# power_electronicsV4_4.net
KiCad netlist of a schematic drawn in EAGLE
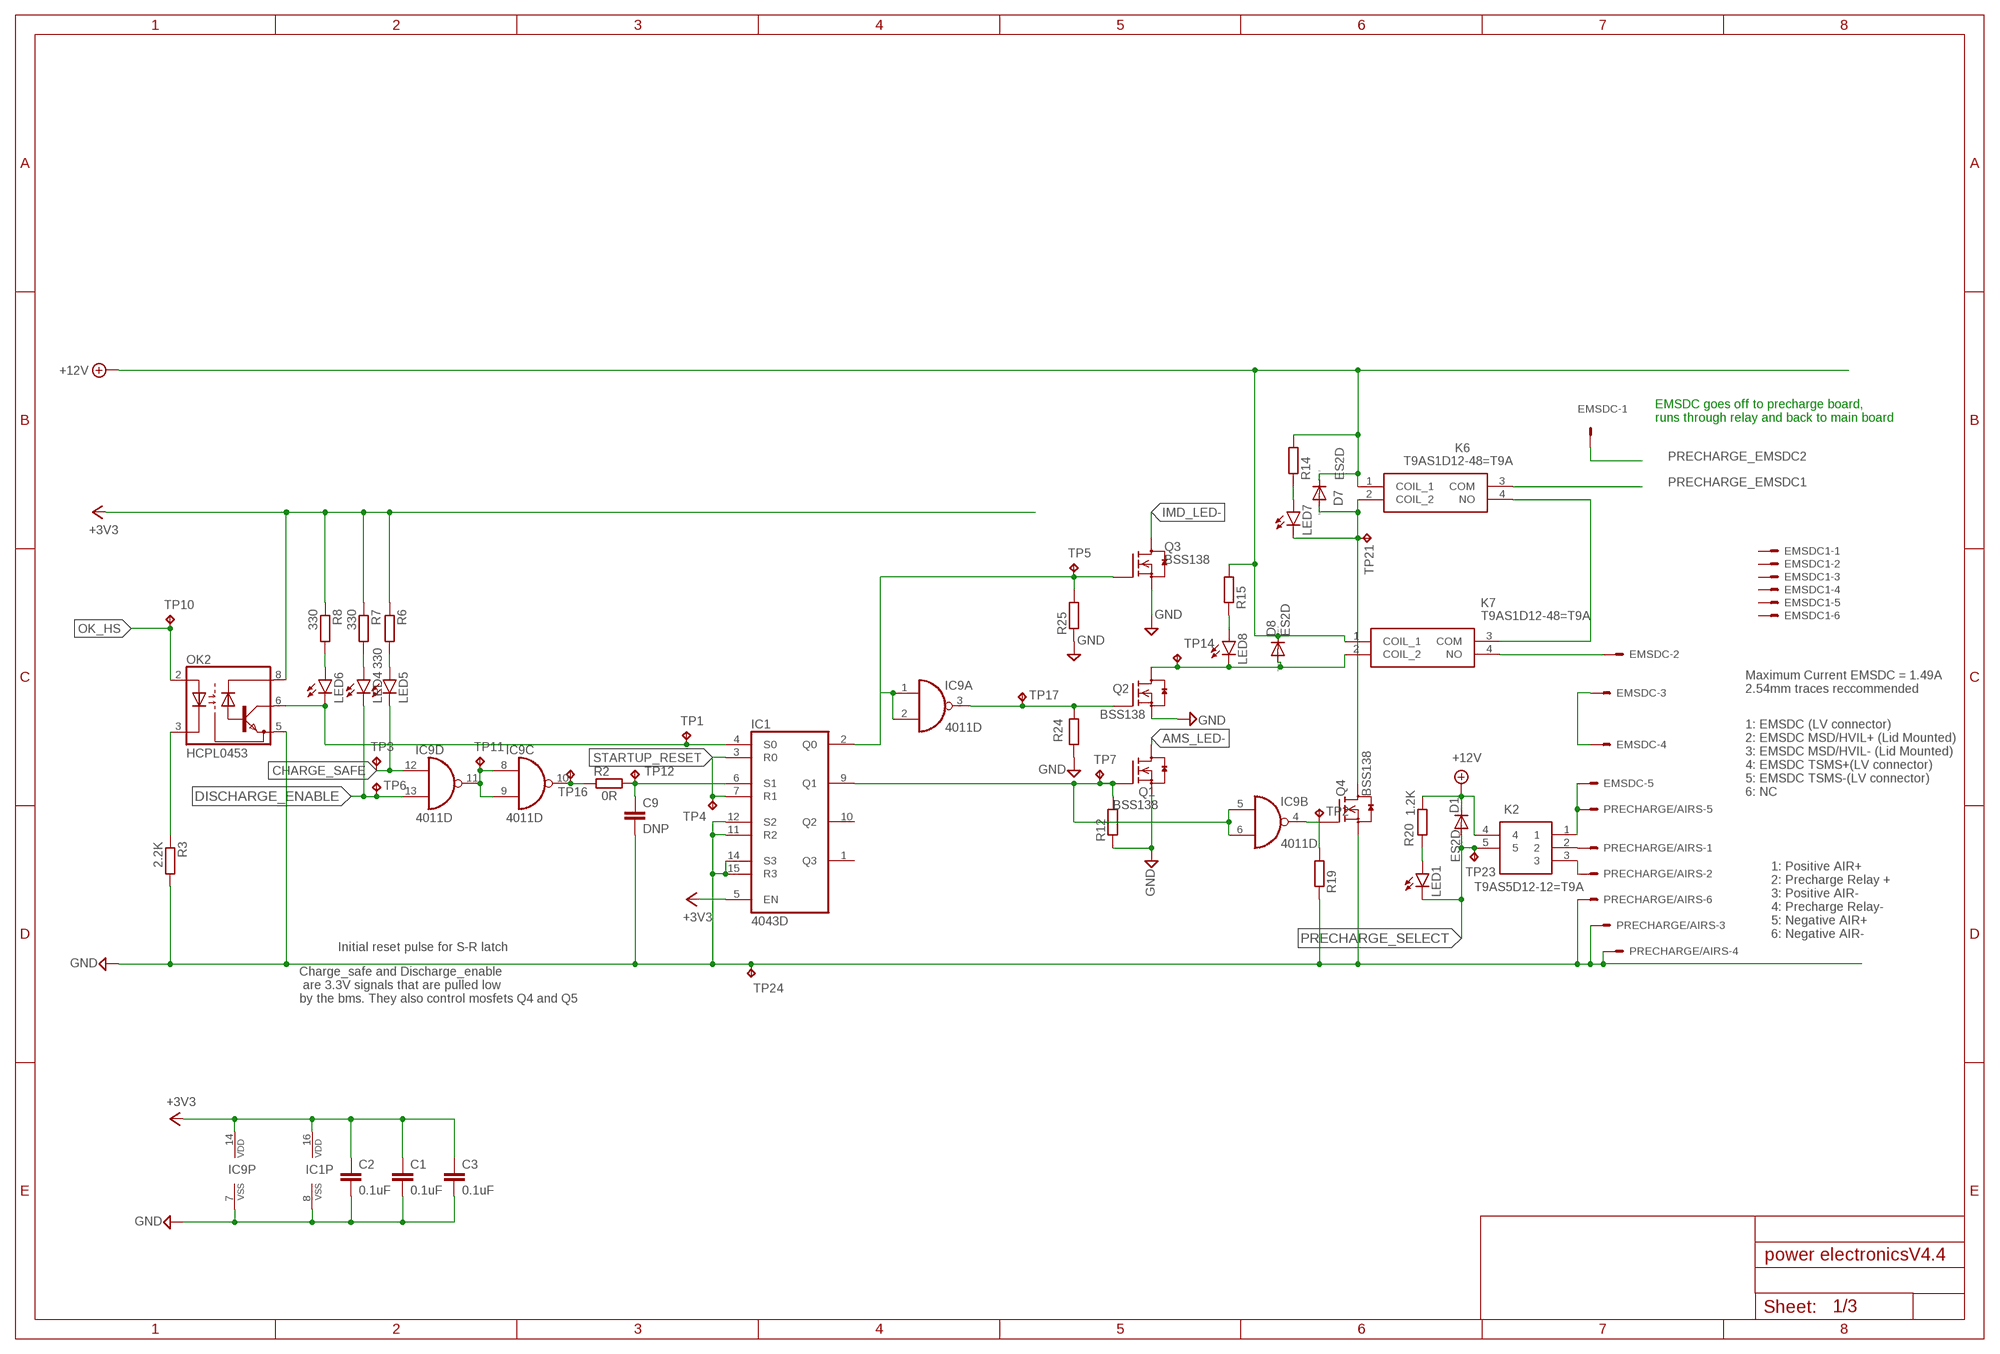
[diagram p0: schematic, sheet 1]
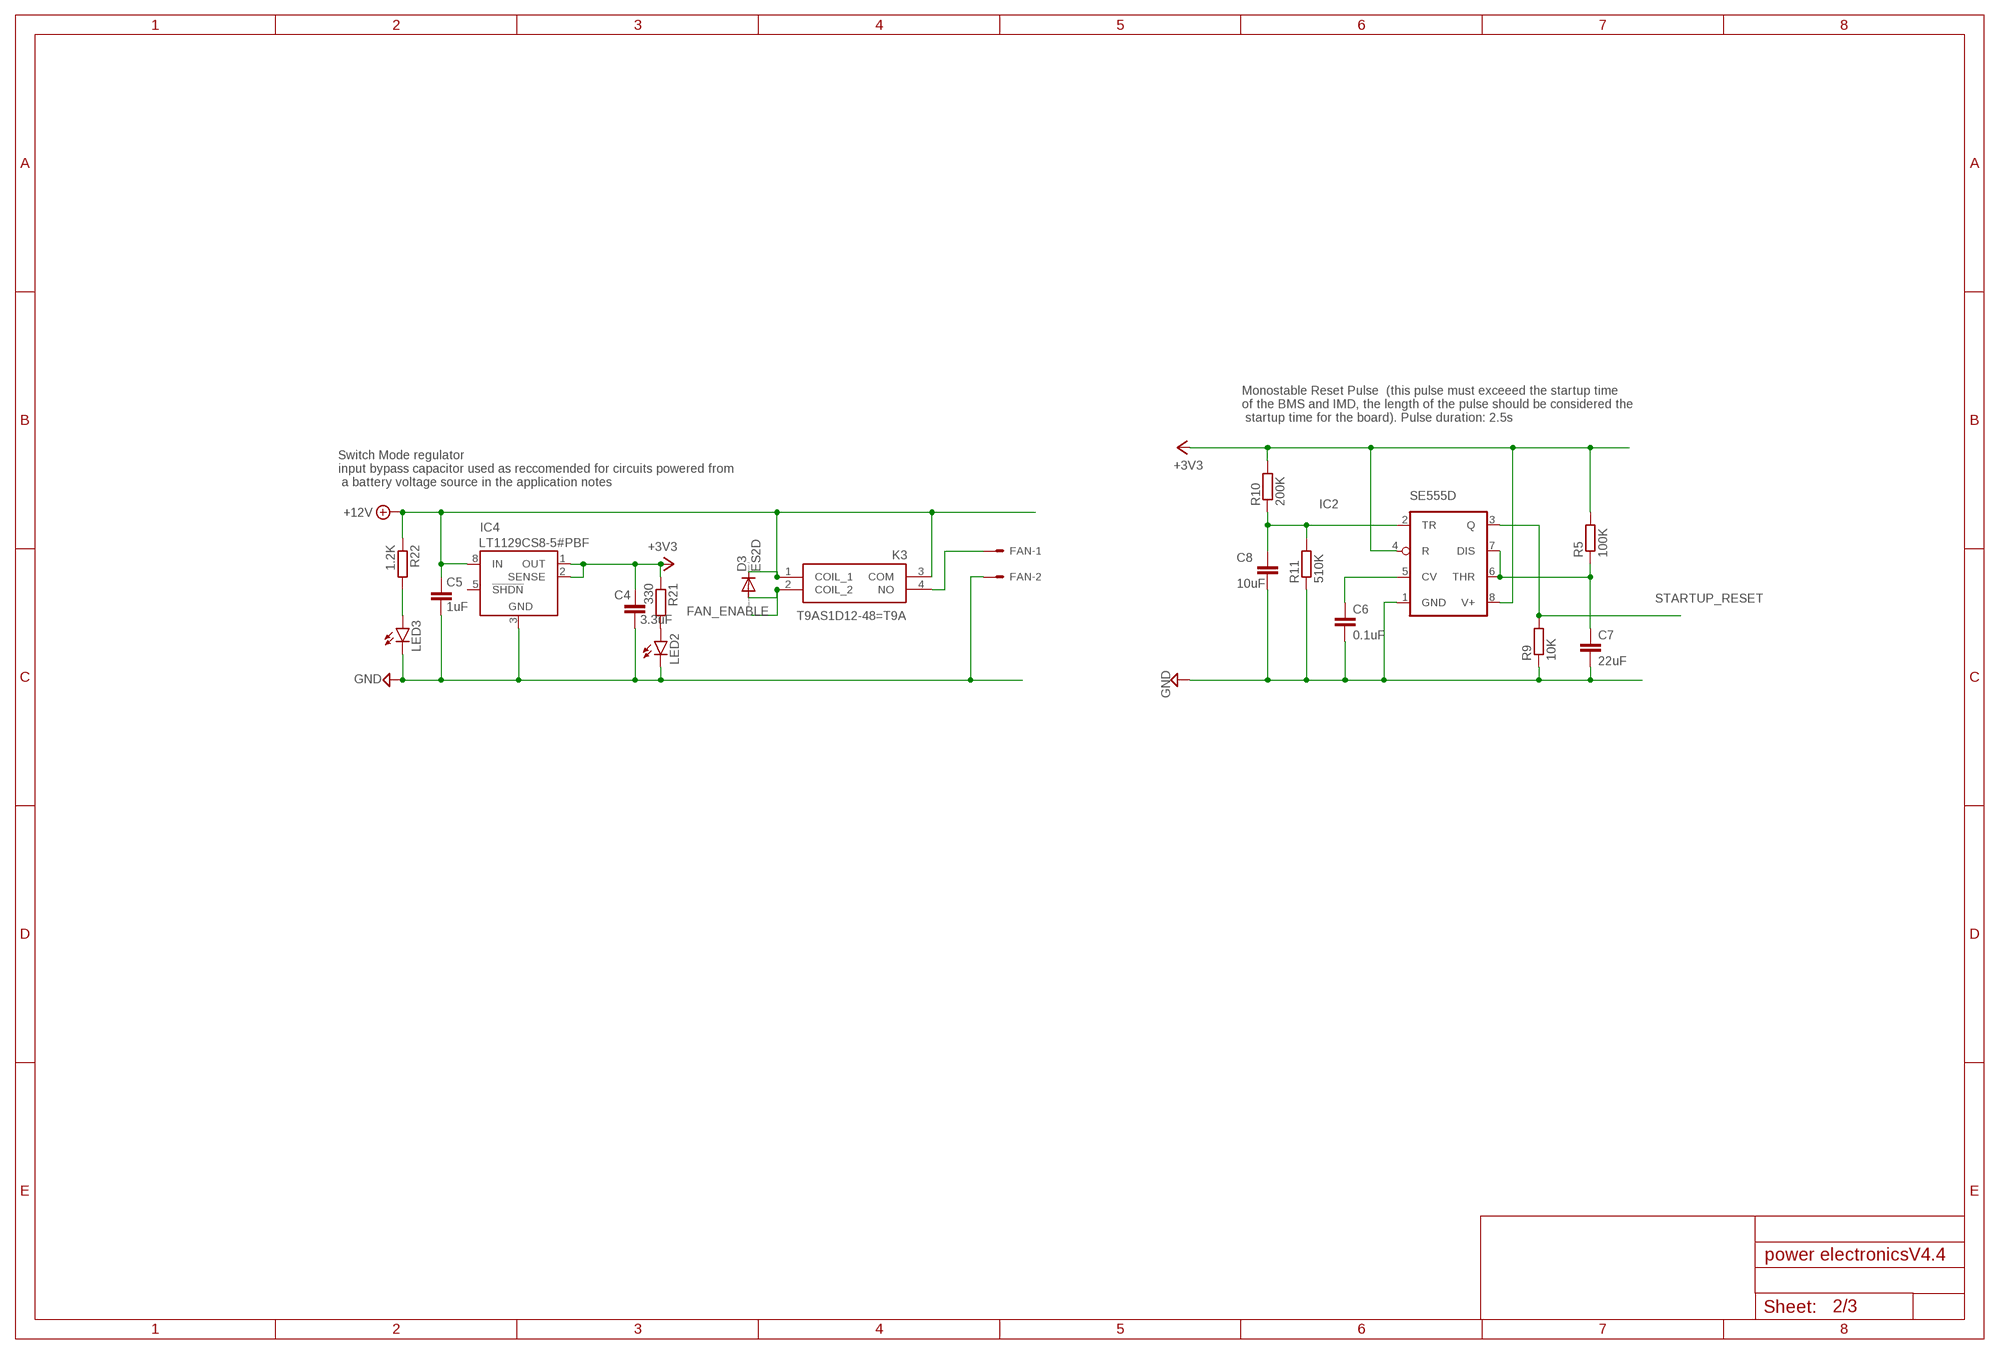
[diagram p1: schematic, sheet 2]
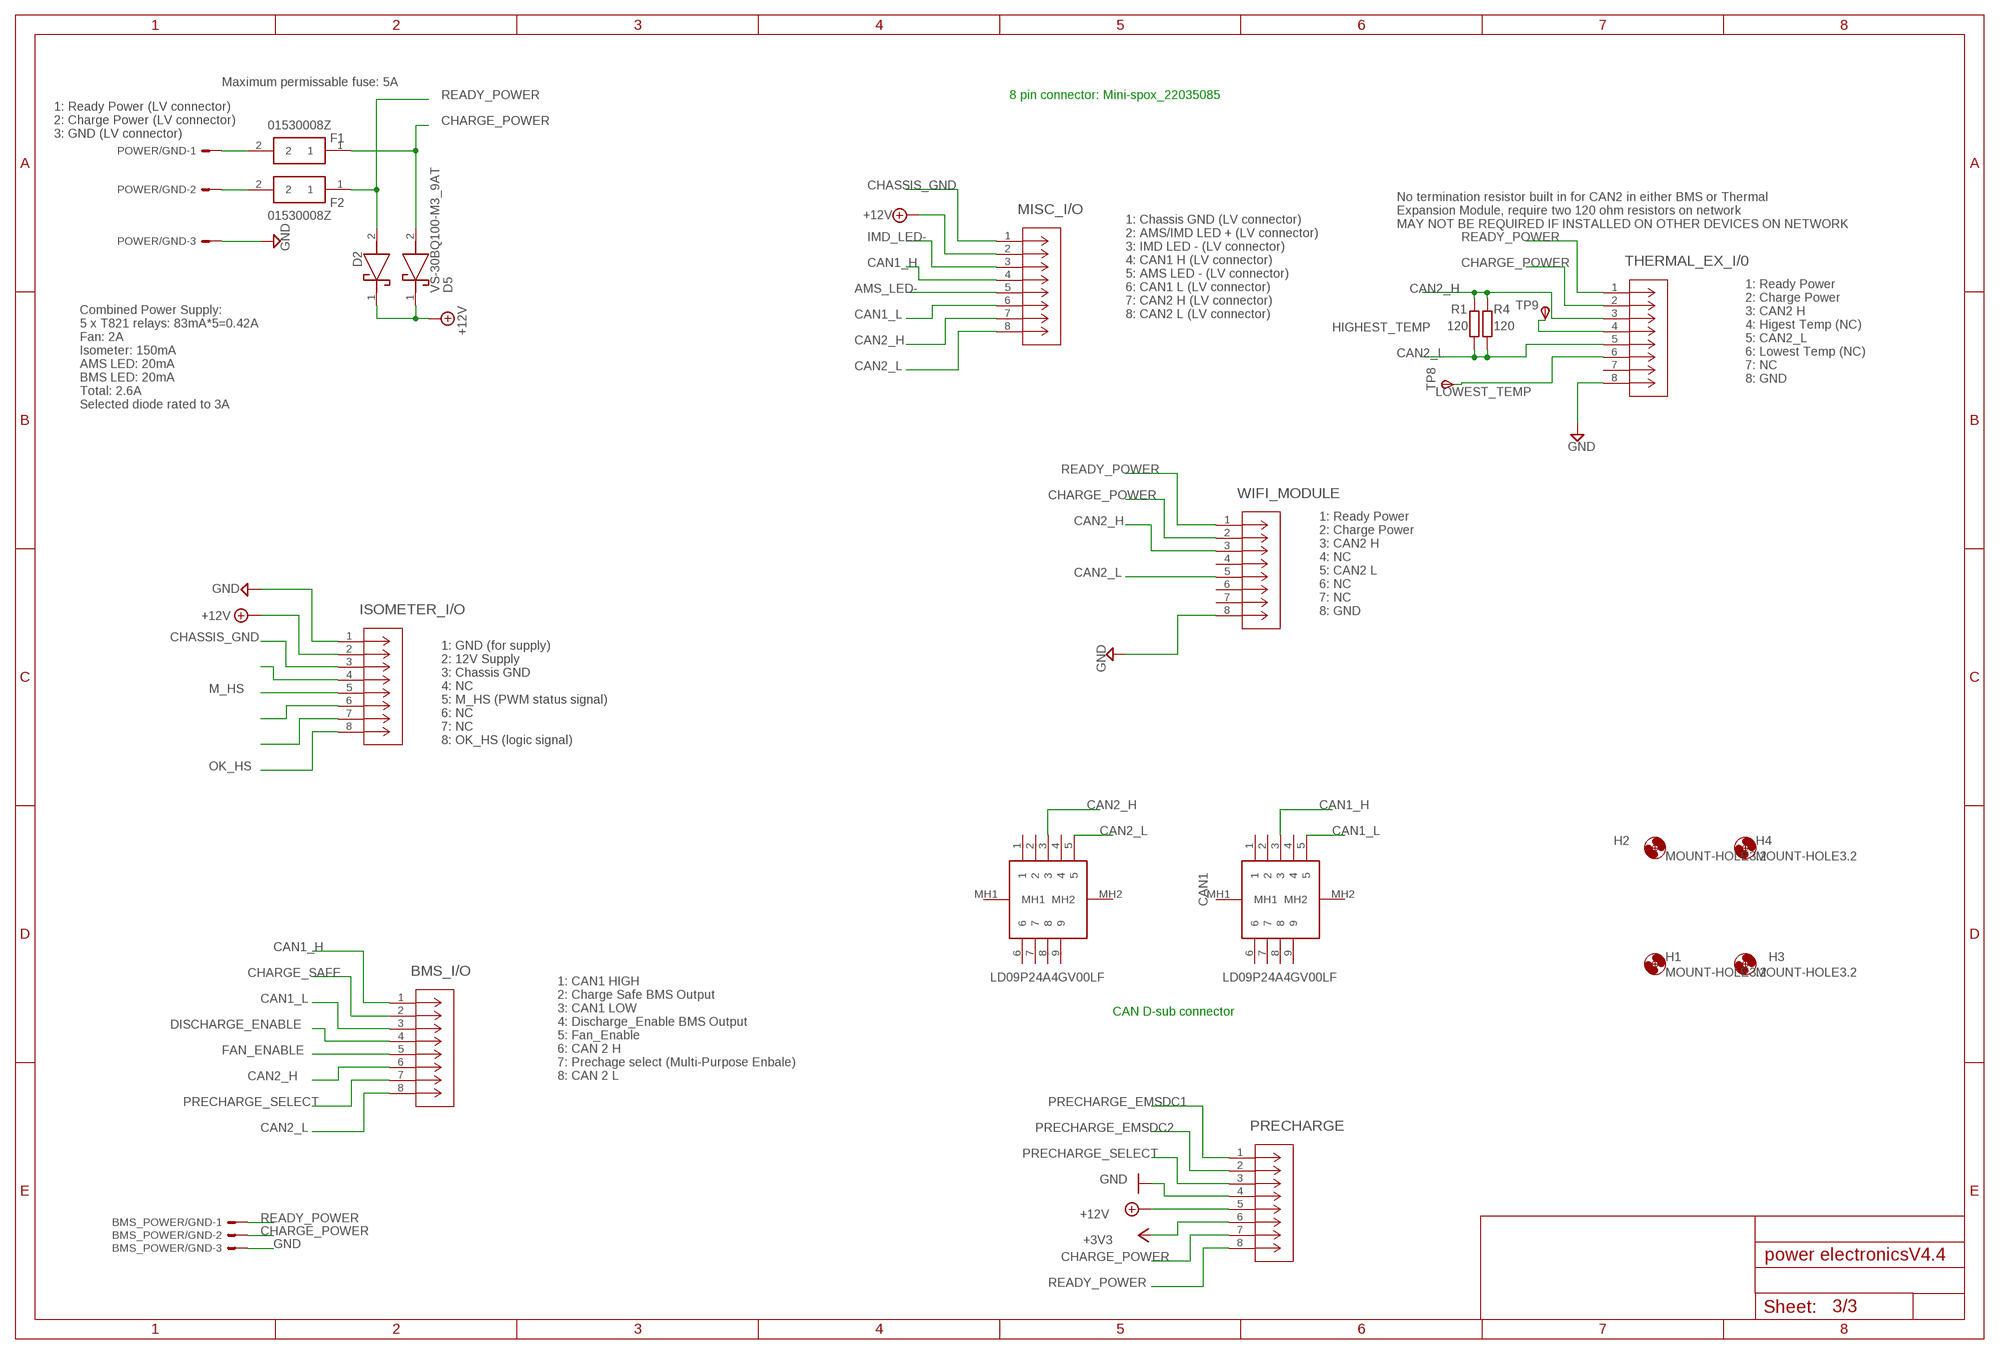
[diagram p2: schematic, sheet 3]

(export (version "E")
  (design (tool "Eeschema 10.0.6"))
  (components
    (comp (ref "BMS_I/O")
      (value "MINI-SPOX_22035085")
      (footprint "eagle-import:CON_22035085_MOL")
      (fields
        (field (name "MANUFACTURER_PART_NUMBER") "22035085")
        (field (name "COPYRIGHT") "Copyright (C) 2023 Ultra Librarian. All rights reserved.")
      )
      (libsource (lib "eagle-import") (part "MINI-SPOX_22035085"))
    )
    (comp (ref "BMS_POWER/GND")
      (value "KK-156-3")
      (footprint "eagle-import:KK-156-3")
      (fields (field (name "MF") "MOLEX"))
      (libsource (lib "eagle-import") (part "KK-156-3"))
    )
    (comp (ref "CAN1")
      (value "LD09P24A4GV00LF")
      (footprint "eagle-import:LD09P24A4GV00LF")
      (fields (field (name "MOUSER_PART_NUMBER") "649-LD09P24A4GV00LF"))
      (libsource (lib "eagle-import") (part "LD09P24A4GV00LF"))
    )
    (comp (ref "CAN2")
      (value "LD09P24A4GV00LF")
      (footprint "eagle-import:LD09P24A4GV00LF")
      (fields (field (name "MOUSER_PART_NUMBER") "649-LD09P24A4GV00LF"))
      (libsource (lib "eagle-import") (part "LD09P24A4GV00LF"))
    )
    (comp (ref "D2")
      (value "VS-30BQ100-M3_9AT")
      (footprint "eagle-import:DIOM7959X262N")
      (fields
        (field (name "MANUFACTURER_PART_NUMBER") "VS-30BQ100-M3/9AT")
        (field (name "MOUSER_PART_NUMBER") "78-VS-30BQ100-M39AT")
      )
      (libsource (lib "eagle-import") (part "VS-30BQ100-M3_9AT"))
    )
    (comp (ref "D5")
      (value "VS-30BQ100-M3_9AT")
      (footprint "eagle-import:DIOM7959X262N")
      (fields
        (field (name "MANUFACTURER_PART_NUMBER") "VS-30BQ100-M3/9AT")
        (field (name "MOUSER_PART_NUMBER") "78-VS-30BQ100-M39AT")
      )
      (libsource (lib "eagle-import") (part "VS-30BQ100-M3_9AT"))
    )
    (comp (ref "F1")
      (value "01530008Z")
      (footprint "eagle-import:01530008")
      (fields (field (name "RS_PART_NUMBER") "3607317"))
      (libsource (lib "eagle-import") (part "01530008Z"))
    )
    (comp (ref "F2")
      (value "01530008Z")
      (footprint "eagle-import:01530008")
      (fields (field (name "RS_PART_NUMBER") "3607317"))
      (libsource (lib "eagle-import") (part "01530008Z"))
    )
    (comp (ref "H1")
      (value "MOUNT-HOLE3.2")
      (footprint "eagle-import:3,2")
      (libsource (lib "eagle-import") (part "MOUNT-HOLE3.2"))
    )
    (comp (ref "H2")
      (value "MOUNT-HOLE3.2")
      (footprint "eagle-import:3,2")
      (libsource (lib "eagle-import") (part "MOUNT-HOLE3.2"))
    )
    (comp (ref "H3")
      (value "MOUNT-HOLE3.2")
      (footprint "eagle-import:3,2")
      (libsource (lib "eagle-import") (part "MOUNT-HOLE3.2"))
    )
    (comp (ref "H4")
      (value "MOUNT-HOLE3.2")
      (footprint "eagle-import:3,2")
      (libsource (lib "eagle-import") (part "MOUNT-HOLE3.2"))
    )
    (comp (ref "ISOMETER_I/O")
      (value "MINI-SPOX_22035085")
      (footprint "eagle-import:CON_22035085_MOL")
      (fields
        (field (name "MANUFACTURER_PART_NUMBER") "22035085")
        (field (name "COPYRIGHT") "Copyright (C) 2023 Ultra Librarian. All rights reserved.")
      )
      (libsource (lib "eagle-import") (part "MINI-SPOX_22035085"))
    )
    (comp (ref "MISC_I/O")
      (value "MINI-SPOX_22035085")
      (footprint "eagle-import:CON_22035085_MOL")
      (fields
        (field (name "MANUFACTURER_PART_NUMBER") "22035085")
        (field (name "COPYRIGHT") "Copyright (C) 2023 Ultra Librarian. All rights reserved.")
      )
      (libsource (lib "eagle-import") (part "MINI-SPOX_22035085"))
    )
    (comp (ref "POWER/GND")
      (value "KK-156-3")
      (footprint "eagle-import:KK-156-3")
      (fields (field (name "MF") "MOLEX"))
      (libsource (lib "eagle-import") (part "KK-156-3"))
    )
    (comp (ref "PRECHARGE")
      (value "MINI-SPOX_22035085")
      (footprint "eagle-import:CON_22035085_MOL")
      (fields
        (field (name "MANUFACTURER_PART_NUMBER") "22035085")
        (field (name "COPYRIGHT") "Copyright (C) 2023 Ultra Librarian. All rights reserved.")
      )
      (libsource (lib "eagle-import") (part "MINI-SPOX_22035085"))
    )
    (comp (ref "R1")
      (value "120")
      (footprint "eagle-import:R1206")
      (libsource (lib "eagle-import") (part "R-EU_R1206"))
    )
    (comp (ref "R4")
      (value "120")
      (footprint "eagle-import:R1206")
      (libsource (lib "eagle-import") (part "R-EU_R1206"))
    )
    (comp (ref "THERMAL_EX_I/0")
      (value "MINI-SPOX_22035085")
      (footprint "eagle-import:CON_22035085_MOL")
      (fields
        (field (name "MANUFACTURER_PART_NUMBER") "22035085")
        (field (name "COPYRIGHT") "Copyright (C) 2023 Ultra Librarian. All rights reserved.")
      )
      (libsource (lib "eagle-import") (part "MINI-SPOX_22035085"))
    )
    (comp (ref "TP8")
      (value "TPSTP11R")
      (footprint "eagle-import:TP11R")
      (libsource (lib "eagle-import") (part "TPSTP11R"))
    )
    (comp (ref "TP9")
      (value "TPSTP11R")
      (footprint "eagle-import:TP11R")
      (libsource (lib "eagle-import") (part "TPSTP11R"))
    )
    (comp (ref "WIFI_MODULE")
      (value "MINI-SPOX_22035085")
      (footprint "eagle-import:CON_22035085_MOL")
      (fields
        (field (name "MANUFACTURER_PART_NUMBER") "22035085")
        (field (name "COPYRIGHT") "Copyright (C) 2023 Ultra Librarian. All rights reserved.")
      )
      (libsource (lib "eagle-import") (part "MINI-SPOX_22035085"))
    )
    (comp (ref "C1")
      (value "0.1uF")
      (footprint "eagle-import:C0805")
      (libsource (lib "eagle-import") (part "C-EUC0805"))
    )
    (comp (ref "C2")
      (value "0.1uF")
      (footprint "eagle-import:C0805")
      (libsource (lib "eagle-import") (part "C-EUC0805"))
    )
    (comp (ref "C3")
      (value "0.1uF")
      (footprint "eagle-import:C0805")
      (libsource (lib "eagle-import") (part "C-EUC0805"))
    )
    (comp (ref "C9")
      (value "DNP")
      (footprint "eagle-import:C0805K")
      (libsource (lib "eagle-import") (part "C-EUC0805K"))
    )
    (comp (ref "D1")
      (value "ES2D")
      (footprint "eagle-import:SMB")
      (libsource (lib "eagle-import") (part "ES2D"))
    )
    (comp (ref "D7")
      (value "ES2D")
      (footprint "eagle-import:SMB")
      (libsource (lib "eagle-import") (part "ES2D"))
    )
    (comp (ref "D8")
      (value "ES2D")
      (footprint "eagle-import:SMB")
      (libsource (lib "eagle-import") (part "ES2D"))
    )
    (comp (ref "EMSDC")
      (value "KK-156-6")
      (footprint "eagle-import:KK-156-6")
      (fields (field (name "MF") "MOLEX"))
      (libsource (lib "eagle-import") (part "KK-156-6"))
    )
    (comp (ref "EMSDC1")
      (value "KK-156-6")
      (footprint "eagle-import:KK-156-6")
      (fields (field (name "MF") "MOLEX"))
      (libsource (lib "eagle-import") (part "KK-156-6"))
    )
    (comp (ref "IC1")
      (value "4043D")
      (footprint "eagle-import:SO16")
      (libsource (lib "eagle-import") (part "4043D"))
    )
    (comp (ref "IC9")
      (value "4011D")
      (footprint "eagle-import:SO14")
      (libsource (lib "eagle-import") (part "4011D"))
    )
    (comp (ref "K2")
      (value "T9AS5D12-12=T9A")
      (footprint "eagle-import:T9AS1D12")
      (fields (field (name "RS_PART_NUMBER") "6802528"))
      (libsource (lib "eagle-import") (part "T9AS5D12-12=T9A"))
    )
    (comp (ref "K6")
      (value "T9AS1D12-48=T9A")
      (footprint "eagle-import:T9AS1D1248T9A")
      (libsource (lib "eagle-import") (part "T9AS1D12-12=T9A_T9AS1D12-48=T9A"))
    )
    (comp (ref "K7")
      (value "T9AS1D12-48=T9A")
      (footprint "eagle-import:T9AS1D1248T9A")
      (libsource (lib "eagle-import") (part "T9AS1D12-12=T9A_T9AS1D12-48=T9A"))
    )
    (comp (ref "LED1")
      (value "LEDSML0805")
      (footprint "eagle-import:SML0805")
      (libsource (lib "eagle-import") (part "LEDSML0805"))
    )
    (comp (ref "LED4")
      (value "LEDSML0805")
      (footprint "eagle-import:SML0805")
      (libsource (lib "eagle-import") (part "LEDSML0805"))
    )
    (comp (ref "LED5")
      (value "LEDSML0805")
      (footprint "eagle-import:SML0805")
      (libsource (lib "eagle-import") (part "LEDSML0805"))
    )
    (comp (ref "LED6")
      (value "LEDSML0805")
      (footprint "eagle-import:SML0805")
      (libsource (lib "eagle-import") (part "LEDSML0805"))
    )
    (comp (ref "LED7")
      (value "LEDSML0805")
      (footprint "eagle-import:SML0805")
      (libsource (lib "eagle-import") (part "LEDSML0805"))
    )
    (comp (ref "LED8")
      (value "LEDSML0805")
      (footprint "eagle-import:SML0805")
      (libsource (lib "eagle-import") (part "LEDSML0805"))
    )
    (comp (ref "OK2")
      (value "HCPL0453")
      (footprint "eagle-import:SOIC08")
      (fields (field (name "MF") "AGILENT TECHNOLOGIES") (field (name "MPN") "HCPL-0453-000E"))
      (libsource (lib "eagle-import") (part "HCPL0453"))
    )
    (comp (ref "PRECHARGE/AIRS")
      (value "KK-156-6")
      (footprint "eagle-import:KK-156-6")
      (fields (field (name "MF") "MOLEX"))
      (libsource (lib "eagle-import") (part "KK-156-6"))
    )
    (comp (ref "Q1")
      (value "BSS138")
      (footprint "eagle-import:SOT23")
      (libsource (lib "eagle-import") (part "BSS138"))
    )
    (comp (ref "Q2")
      (value "BSS138")
      (footprint "eagle-import:SOT23")
      (libsource (lib "eagle-import") (part "BSS138"))
    )
    (comp (ref "Q3")
      (value "BSS138")
      (footprint "eagle-import:SOT23")
      (libsource (lib "eagle-import") (part "BSS138"))
    )
    (comp (ref "Q4")
      (value "BSS138")
      (footprint "eagle-import:SOT23")
      (libsource (lib "eagle-import") (part "BSS138"))
    )
    (comp (ref "R2")
      (value "0R")
      (footprint "eagle-import:R0805")
      (libsource (lib "eagle-import") (part "R-EU_R0805"))
    )
    (comp (ref "R3")
      (value "2.2K")
      (footprint "eagle-import:R0805")
      (libsource (lib "eagle-import") (part "R-EU_R0805"))
    )
    (comp (ref "R6")
      (value "330")
      (footprint "eagle-import:R0805")
      (libsource (lib "eagle-import") (part "R-EU_R0805"))
    )
    (comp (ref "R7")
      (value "330")
      (footprint "eagle-import:R0805")
      (libsource (lib "eagle-import") (part "R-EU_R0805"))
    )
    (comp (ref "R8")
      (value "330")
      (footprint "eagle-import:R0805")
      (libsource (lib "eagle-import") (part "R-EU_R0805"))
    )
    (comp (ref "R12")
      (value "R-EU_R0805")
      (footprint "eagle-import:R0805")
      (libsource (lib "eagle-import") (part "R-EU_R0805"))
    )
    (comp (ref "R14")
      (value "R-EU_R0805")
      (footprint "eagle-import:R0805")
      (libsource (lib "eagle-import") (part "R-EU_R0805"))
    )
    (comp (ref "R15")
      (value "R-EU_R0805")
      (footprint "eagle-import:R0805")
      (libsource (lib "eagle-import") (part "R-EU_R0805"))
    )
    (comp (ref "R19")
      (value "R-EU_R0805")
      (footprint "eagle-import:R0805")
      (libsource (lib "eagle-import") (part "R-EU_R0805"))
    )
    (comp (ref "R20")
      (value "1.2K")
      (footprint "eagle-import:R0805")
      (libsource (lib "eagle-import") (part "R-EU_R0805"))
    )
    (comp (ref "R24")
      (value "R-EU_R0805")
      (footprint "eagle-import:R0805")
      (libsource (lib "eagle-import") (part "R-EU_R0805"))
    )
    (comp (ref "R25")
      (value "R-EU_R0805")
      (footprint "eagle-import:R0805")
      (libsource (lib "eagle-import") (part "R-EU_R0805"))
    )
    (comp (ref "TP1")
      (value "TPPAD1-17")
      (footprint "eagle-import:P1-17")
      (libsource (lib "eagle-import") (part "TPPAD1-17"))
    )
    (comp (ref "TP2")
      (value "TPPAD1-17")
      (footprint "eagle-import:P1-17")
      (libsource (lib "eagle-import") (part "TPPAD1-17"))
    )
    (comp (ref "TP3")
      (value "TPPAD1-17")
      (footprint "eagle-import:P1-17")
      (libsource (lib "eagle-import") (part "TPPAD1-17"))
    )
    (comp (ref "TP4")
      (value "TPPAD1-17")
      (footprint "eagle-import:P1-17")
      (libsource (lib "eagle-import") (part "TPPAD1-17"))
    )
    (comp (ref "TP5")
      (value "TPPAD1-17")
      (footprint "eagle-import:P1-17")
      (libsource (lib "eagle-import") (part "TPPAD1-17"))
    )
    (comp (ref "TP6")
      (value "TPPAD1-17")
      (footprint "eagle-import:P1-17")
      (libsource (lib "eagle-import") (part "TPPAD1-17"))
    )
    (comp (ref "TP7")
      (value "TPPAD1-17")
      (footprint "eagle-import:P1-17")
      (libsource (lib "eagle-import") (part "TPPAD1-17"))
    )
    (comp (ref "TP10")
      (value "TPPAD1-17")
      (footprint "eagle-import:P1-17")
      (libsource (lib "eagle-import") (part "TPPAD1-17"))
    )
    (comp (ref "TP11")
      (value "TPPAD1-17")
      (footprint "eagle-import:P1-17")
      (libsource (lib "eagle-import") (part "TPPAD1-17"))
    )
    (comp (ref "TP12")
      (value "TPPAD1-17")
      (footprint "eagle-import:P1-17")
      (libsource (lib "eagle-import") (part "TPPAD1-17"))
    )
    (comp (ref "TP14")
      (value "TPPAD1-17")
      (footprint "eagle-import:P1-17")
      (libsource (lib "eagle-import") (part "TPPAD1-17"))
    )
    (comp (ref "TP16")
      (value "TPPAD1-17")
      (footprint "eagle-import:P1-17")
      (libsource (lib "eagle-import") (part "TPPAD1-17"))
    )
    (comp (ref "TP17")
      (value "TPPAD1-17")
      (footprint "eagle-import:P1-17")
      (libsource (lib "eagle-import") (part "TPPAD1-17"))
    )
    (comp (ref "TP21")
      (value "TPPAD1-17")
      (footprint "eagle-import:P1-17")
      (libsource (lib "eagle-import") (part "TPPAD1-17"))
    )
    (comp (ref "TP23")
      (value "TPPAD1-17")
      (footprint "eagle-import:P1-17")
      (libsource (lib "eagle-import") (part "TPPAD1-17"))
    )
    (comp (ref "TP24")
      (value "TPPAD1-17")
      (footprint "eagle-import:P1-17")
      (libsource (lib "eagle-import") (part "TPPAD1-17"))
    )
    (comp (ref "C4")
      (value "3.3uF")
      (footprint "eagle-import:C0805")
      (libsource (lib "eagle-import") (part "C-EUC0805"))
    )
    (comp (ref "C5")
      (value "1uF")
      (footprint "eagle-import:C0805")
      (libsource (lib "eagle-import") (part "C-EUC0805"))
    )
    (comp (ref "C6")
      (value "0.1uF")
      (footprint "eagle-import:C0805")
      (libsource (lib "eagle-import") (part "C-EUC0805"))
    )
    (comp (ref "C7")
      (value "22uF")
      (footprint "eagle-import:C1206")
      (libsource (lib "eagle-import") (part "C-EUC1206"))
    )
    (comp (ref "C8")
      (value "10uF")
      (footprint "eagle-import:C0805")
      (libsource (lib "eagle-import") (part "C-EUC0805"))
    )
    (comp (ref "D3")
      (value "ES2D")
      (footprint "eagle-import:SMB")
      (libsource (lib "eagle-import") (part "ES2D"))
    )
    (comp (ref "FAN")
      (value "KK-156-2")
      (footprint "eagle-import:KK-156-2")
      (fields (field (name "MF") "MOLEX"))
      (libsource (lib "eagle-import") (part "KK-156-2"))
    )
    (comp (ref "IC2")
      (value "SE555D")
      (footprint "eagle-import:SO08")
      (libsource (lib "eagle-import") (part "555DSE"))
    )
    (comp (ref "IC4")
      (value "LT1129CS8")
      (footprint "eagle-import:SOIC8")
      (fields (field (name "MPN") "LT1129CS8-5#PBF"))
      (libsource (lib "eagle-import") (part "LT1129CS8"))
    )
    (comp (ref "K3")
      (value "T9AS1D12-48=T9A")
      (footprint "eagle-import:T9AS1D1248T9A")
      (fields (field (name "RS_PART_NUMBER") "6802534P"))
      (libsource (lib "eagle-import") (part "T9AS1D12-48=T9A"))
    )
    (comp (ref "LED2")
      (value "LEDSML0805")
      (footprint "eagle-import:SML0805")
      (libsource (lib "eagle-import") (part "LEDSML0805"))
    )
    (comp (ref "LED3")
      (value "LEDSML0805")
      (footprint "eagle-import:SML0805")
      (libsource (lib "eagle-import") (part "LEDSML0805"))
    )
    (comp (ref "R5")
      (value "100K")
      (footprint "eagle-import:R0805")
      (libsource (lib "eagle-import") (part "R-EU_R0805"))
    )
    (comp (ref "R9")
      (value "10K")
      (footprint "eagle-import:R0805")
      (libsource (lib "eagle-import") (part "R-EU_R0805"))
    )
    (comp (ref "R10")
      (value "200K")
      (footprint "eagle-import:R0805")
      (libsource (lib "eagle-import") (part "R-EU_R0805"))
    )
    (comp (ref "R11")
      (value "510K")
      (footprint "eagle-import:R0805")
      (libsource (lib "eagle-import") (part "R-EU_R0805"))
    )
    (comp (ref "R21")
      (value "330")
      (footprint "eagle-import:R0805")
      (libsource (lib "eagle-import") (part "R-EU_R0805"))
    )
    (comp (ref "R22")
      (value "1.2K")
      (footprint "eagle-import:R0805")
      (libsource (lib "eagle-import") (part "R-EU_R0805"))
    )
  )
  (nets
    (net (code "1") (name "+3V3") (class "Default")
      (node (ref "C1") (pin "1") (pinfunction "1_1") (pintype "passive"))
      (node (ref "C2") (pin "1") (pinfunction "1_1") (pintype "passive"))
      (node (ref "C3") (pin "1") (pinfunction "1_1") (pintype "passive"))
      (node (ref "C4") (pin "1") (pinfunction "1_1") (pintype "passive"))
      (node (ref "IC1") (pin "16") (pinfunction "VDD_16") (pintype "power_in"))
      (node (ref "IC1") (pin "5") (pinfunction "EN_5") (pintype "input"))
      (node (ref "IC2") (pin "4") (pinfunction "R_4") (pintype "input"))
      (node (ref "IC2") (pin "8") (pinfunction "V+_8") (pintype "power_in"))
      (node (ref "IC4") (pin "1") (pinfunction "OUT_1") (pintype "output"))
      (node (ref "IC4") (pin "2") (pinfunction "SENSE_2") (pintype "input"))
      (node (ref "IC9") (pin "14") (pinfunction "VDD_14") (pintype "power_in"))
      (node (ref "OK2") (pin "8") (pinfunction "VCC_8") (pintype "passive"))
      (node (ref "PRECHARGE") (pin "6") (pinfunction "6_6") (pintype "passive"))
      (node (ref "R10") (pin "2") (pinfunction "2_2") (pintype "passive"))
      (node (ref "R21") (pin "1") (pinfunction "1_1") (pintype "passive"))
      (node (ref "R5") (pin "2") (pinfunction "2_2") (pintype "passive"))
      (node (ref "R6") (pin "1") (pinfunction "1_1") (pintype "passive"))
      (node (ref "R7") (pin "1") (pinfunction "1_1") (pintype "passive"))
      (node (ref "R8") (pin "1") (pinfunction "1_1") (pintype "passive"))
    )
    (net (code "2") (name "+12V") (class "Default")
      (node (ref "C5") (pin "1") (pinfunction "1_1") (pintype "passive"))
      (node (ref "D1") (pin "C") (pinfunction "C_C") (pintype "passive"))
      (node (ref "D2") (pin "1") (pinfunction "K_1") (pintype "bidirectional"))
      (node (ref "D3") (pin "C") (pinfunction "C_C") (pintype "passive"))
      (node (ref "D5") (pin "1") (pinfunction "K_1") (pintype "bidirectional"))
      (node (ref "D7") (pin "C") (pinfunction "C_C") (pintype "passive"))
      (node (ref "D8") (pin "C") (pinfunction "C_C") (pintype "passive"))
      (node (ref "IC4") (pin "8") (pinfunction "IN_8") (pintype "input"))
      (node (ref "ISOMETER_I/O") (pin "2") (pinfunction "2_2") (pintype "passive"))
      (node (ref "K2") (pin "4") (pinfunction "4_4") (pintype "bidirectional"))
      (node (ref "K3") (pin "1") (pinfunction "COIL_1_1") (pintype "bidirectional"))
      (node (ref "K3") (pin "3") (pinfunction "COM_3") (pintype "bidirectional"))
      (node (ref "K6") (pin "1") (pinfunction "COIL_1_1") (pintype "bidirectional"))
      (node (ref "K7") (pin "1") (pinfunction "COIL_1_1") (pintype "bidirectional"))
      (node (ref "MISC_I/O") (pin "2") (pinfunction "2_2") (pintype "passive"))
      (node (ref "PRECHARGE") (pin "5") (pinfunction "5_5") (pintype "passive"))
      (node (ref "R14") (pin "2") (pinfunction "2_2") (pintype "passive"))
      (node (ref "R15") (pin "2") (pinfunction "2_2") (pintype "passive"))
      (node (ref "R20") (pin "1") (pinfunction "1_1") (pintype "passive"))
      (node (ref "R22") (pin "1") (pinfunction "1_1") (pintype "passive"))
    )
    (net (code "3") (name "AMS_LED-") (class "Default")
      (node (ref "MISC_I/O") (pin "5") (pinfunction "5_5") (pintype "passive"))
      (node (ref "Q1") (pin "3") (pinfunction "D_3") (pintype "passive"))
    )
    (net (code "4") (name "CAN1_H") (class "Default")
      (node (ref "BMS_I/O") (pin "1") (pinfunction "1_1") (pintype "passive"))
      (node (ref "CAN1") (pin "3") (pinfunction "3_3") (pintype "bidirectional"))
      (node (ref "MISC_I/O") (pin "4") (pinfunction "4_4") (pintype "passive"))
    )
    (net (code "5") (name "CAN1_L") (class "Default")
      (node (ref "BMS_I/O") (pin "3") (pinfunction "3_3") (pintype "passive"))
      (node (ref "CAN1") (pin "5") (pinfunction "5_5") (pintype "bidirectional"))
      (node (ref "MISC_I/O") (pin "6") (pinfunction "6_6") (pintype "passive"))
    )
    (net (code "6") (name "CAN2_H") (class "Default")
      (node (ref "BMS_I/O") (pin "6") (pinfunction "6_6") (pintype "passive"))
      (node (ref "CAN2") (pin "3") (pinfunction "3_3") (pintype "bidirectional"))
      (node (ref "MISC_I/O") (pin "7") (pinfunction "7_7") (pintype "passive"))
      (node (ref "R1") (pin "1") (pinfunction "1_1") (pintype "passive"))
      (node (ref "R4") (pin "1") (pinfunction "1_1") (pintype "passive"))
      (node (ref "THERMAL_EX_I/0") (pin "3") (pinfunction "3_3") (pintype "passive"))
      (node (ref "WIFI_MODULE") (pin "3") (pinfunction "3_3") (pintype "passive"))
    )
    (net (code "7") (name "CAN2_L") (class "Default")
      (node (ref "BMS_I/O") (pin "8") (pinfunction "8_8") (pintype "passive"))
      (node (ref "CAN2") (pin "5") (pinfunction "5_5") (pintype "bidirectional"))
      (node (ref "MISC_I/O") (pin "8") (pinfunction "8_8") (pintype "passive"))
      (node (ref "R1") (pin "2") (pinfunction "2_2") (pintype "passive"))
      (node (ref "R4") (pin "2") (pinfunction "2_2") (pintype "passive"))
      (node (ref "THERMAL_EX_I/0") (pin "5") (pinfunction "5_5") (pintype "passive"))
      (node (ref "WIFI_MODULE") (pin "5") (pinfunction "5_5") (pintype "passive"))
    )
    (net (code "8") (name "CHARGE_POWER") (class "Default")
      (node (ref "BMS_POWER/GND") (pin "2") (pinfunction "S_2") (pintype "passive"))
      (node (ref "D5") (pin "2") (pinfunction "A_2") (pintype "bidirectional"))
      (node (ref "F1") (pin "1") (pinfunction "1_1") (pintype "bidirectional"))
      (node (ref "PRECHARGE") (pin "7") (pinfunction "7_7") (pintype "passive"))
      (node (ref "THERMAL_EX_I/0") (pin "2") (pinfunction "2_2") (pintype "passive"))
      (node (ref "WIFI_MODULE") (pin "2") (pinfunction "2_2") (pintype "passive"))
    )
    (net (code "9") (name "CHARGE_SAFE") (class "Default")
      (node (ref "BMS_I/O") (pin "2") (pinfunction "2_2") (pintype "passive"))
      (node (ref "IC9") (pin "12") (pinfunction "I0_12") (pintype "input"))
      (node (ref "LED5") (pin "C") (pinfunction "C_C") (pintype "passive"))
      (node (ref "TP3") (pin "TP") (pinfunction "TP_TP") (pintype "input"))
    )
    (net (code "10") (name "CHASSIS_GND") (class "Default")
      (node (ref "ISOMETER_I/O") (pin "3") (pinfunction "3_3") (pintype "passive"))
      (node (ref "MISC_I/O") (pin "1") (pinfunction "1_1") (pintype "passive"))
    )
    (net (code "11") (name "DISCHARGE_ENABLE") (class "Default")
      (node (ref "BMS_I/O") (pin "4") (pinfunction "4_4") (pintype "passive"))
      (node (ref "IC1") (pin "9") (pinfunction "Q1_9") (pintype "output"))
      (node (ref "IC9") (pin "13") (pinfunction "I1_13") (pintype "input"))
      (node (ref "IC9") (pin "5") (pinfunction "I0_5") (pintype "input"))
      (node (ref "IC9") (pin "6") (pinfunction "I1_6") (pintype "input"))
      (node (ref "LED4") (pin "C") (pinfunction "C_C") (pintype "passive"))
      (node (ref "Q1") (pin "1") (pinfunction "G_1") (pintype "passive"))
      (node (ref "R12") (pin "2") (pinfunction "2_2") (pintype "passive"))
      (node (ref "TP6") (pin "TP") (pinfunction "TP_TP") (pintype "input"))
      (node (ref "TP7") (pin "TP") (pinfunction "TP_TP") (pintype "input"))
    )
    (net (code "12") (name "FAN_ENABLE") (class "Default")
      (node (ref "BMS_I/O") (pin "5") (pinfunction "5_5") (pintype "passive"))
      (node (ref "D3") (pin "A") (pinfunction "A_A") (pintype "passive"))
      (node (ref "K3") (pin "2") (pinfunction "COIL_2_2") (pintype "bidirectional"))
    )
    (net (code "13") (name "GND") (class "Default")
      (node (ref "BMS_POWER/GND") (pin "3") (pinfunction "S_3") (pintype "passive"))
      (node (ref "C1") (pin "2") (pinfunction "2_2") (pintype "passive"))
      (node (ref "C2") (pin "2") (pinfunction "2_2") (pintype "passive"))
      (node (ref "C3") (pin "2") (pinfunction "2_2") (pintype "passive"))
      (node (ref "C4") (pin "2") (pinfunction "2_2") (pintype "passive"))
      (node (ref "C5") (pin "2") (pinfunction "2_2") (pintype "passive"))
      (node (ref "C6") (pin "2") (pinfunction "2_2") (pintype "passive"))
      (node (ref "C7") (pin "2") (pinfunction "2_2") (pintype "passive"))
      (node (ref "C8") (pin "2") (pinfunction "2_2") (pintype "passive"))
      (node (ref "C9") (pin "2") (pinfunction "2_2") (pintype "passive"))
      (node (ref "FAN") (pin "2") (pinfunction "S_2") (pintype "passive"))
      (node (ref "IC1") (pin "11") (pinfunction "R2_11") (pintype "input"))
      (node (ref "IC1") (pin "12") (pinfunction "S2_12") (pintype "input"))
      (node (ref "IC1") (pin "14") (pinfunction "S3_14") (pintype "input"))
      (node (ref "IC1") (pin "15") (pinfunction "R3_15") (pintype "input"))
      (node (ref "IC1") (pin "8") (pinfunction "VSS_8") (pintype "power_in"))
      (node (ref "IC2") (pin "1") (pinfunction "GND_1") (pintype "power_in"))
      (node (ref "IC4") (pin "3") (pinfunction "GND_3") (pintype "power_in"))
      (node (ref "IC9") (pin "7") (pinfunction "VSS_7") (pintype "power_in"))
      (node (ref "ISOMETER_I/O") (pin "1") (pinfunction "1_1") (pintype "passive"))
      (node (ref "LED2") (pin "C") (pinfunction "C_C") (pintype "passive"))
      (node (ref "LED3") (pin "C") (pinfunction "C_C") (pintype "passive"))
      (node (ref "OK2") (pin "5") (pinfunction "GND_5") (pintype "passive"))
      (node (ref "POWER/GND") (pin "3") (pinfunction "S_3") (pintype "passive"))
      (node (ref "PRECHARGE") (pin "4") (pinfunction "4_4") (pintype "passive"))
      (node (ref "PRECHARGE/AIRS") (pin "3") (pinfunction "S_3") (pintype "passive"))
      (node (ref "PRECHARGE/AIRS") (pin "4") (pinfunction "S_4") (pintype "passive"))
      (node (ref "PRECHARGE/AIRS") (pin "6") (pinfunction "S_6") (pintype "passive"))
      (node (ref "Q1") (pin "2") (pinfunction "S_2") (pintype "passive"))
      (node (ref "Q2") (pin "2") (pinfunction "S_2") (pintype "passive"))
      (node (ref "Q3") (pin "2") (pinfunction "S_2") (pintype "passive"))
      (node (ref "Q4") (pin "2") (pinfunction "S_2") (pintype "passive"))
      (node (ref "R11") (pin "1") (pinfunction "1_1") (pintype "passive"))
      (node (ref "R12") (pin "1") (pinfunction "1_1") (pintype "passive"))
      (node (ref "R19") (pin "1") (pinfunction "1_1") (pintype "passive"))
      (node (ref "R24") (pin "1") (pinfunction "1_1") (pintype "passive"))
      (node (ref "R25") (pin "1") (pinfunction "1_1") (pintype "passive"))
      (node (ref "R3") (pin "2") (pinfunction "2_2") (pintype "passive"))
      (node (ref "R9") (pin "1") (pinfunction "1_1") (pintype "passive"))
      (node (ref "THERMAL_EX_I/0") (pin "8") (pinfunction "8_8") (pintype "passive"))
      (node (ref "TP24") (pin "TP") (pinfunction "TP_TP") (pintype "input"))
      (node (ref "WIFI_MODULE") (pin "8") (pinfunction "8_8") (pintype "passive"))
    )
    (net (code "14") (name "HIGHEST_TEMP") (class "Default")
      (node (ref "THERMAL_EX_I/0") (pin "4") (pinfunction "4_4") (pintype "passive"))
      (node (ref "TP9") (pin "TP") (pinfunction "PP_TP") (pintype "input"))
    )
    (net (code "15") (name "IMD_LED-") (class "Default")
      (node (ref "MISC_I/O") (pin "3") (pinfunction "3_3") (pintype "passive"))
      (node (ref "Q3") (pin "3") (pinfunction "D_3") (pintype "passive"))
    )
    (net (code "16") (name "LOWEST_TEMP") (class "Default")
      (node (ref "THERMAL_EX_I/0") (pin "6") (pinfunction "6_6") (pintype "passive"))
      (node (ref "TP8") (pin "TP") (pinfunction "PP_TP") (pintype "input"))
    )
    (net (code "17") (name "M_HS") (class "Default")
      (node (ref "ISOMETER_I/O") (pin "5") (pinfunction "5_5") (pintype "passive"))
    )
    (net (code "18") (name "Net-(EMSDCB-S)") (class "Default")
      (node (ref "EMSDC") (pin "2") (pinfunction "S_2") (pintype "passive"))
      (node (ref "K7") (pin "4") (pinfunction "NO_4") (pintype "bidirectional"))
    )
    (net (code "19") (name "Net-(EMSDCC-S)") (class "Default")
      (node (ref "EMSDC") (pin "3") (pinfunction "S_3") (pintype "passive"))
      (node (ref "EMSDC") (pin "4") (pinfunction "S_4") (pintype "passive"))
    )
    (net (code "20") (name "Net-(EMSDCE-S)") (class "Default")
      (node (ref "EMSDC") (pin "5") (pinfunction "S_5") (pintype "passive"))
      (node (ref "K2") (pin "1") (pinfunction "1_1") (pintype "bidirectional"))
      (node (ref "PRECHARGE/AIRS") (pin "5") (pinfunction "S_5") (pintype "passive"))
    )
    (net (code "21") (name "Net-(FANA-S)") (class "Default")
      (node (ref "FAN") (pin "1") (pinfunction "S_1") (pintype "passive"))
      (node (ref "K3") (pin "4") (pinfunction "NO_4") (pintype "bidirectional"))
    )
    (net (code "22") (name "Net-(IC1A-Q0)") (class "Default")
      (node (ref "IC1") (pin "2") (pinfunction "Q0_2") (pintype "output"))
      (node (ref "IC9") (pin "1") (pinfunction "I0_1") (pintype "input"))
      (node (ref "IC9") (pin "2") (pinfunction "I1_2") (pintype "input"))
      (node (ref "Q3") (pin "1") (pinfunction "G_1") (pintype "passive"))
      (node (ref "R25") (pin "2") (pinfunction "2_2") (pintype "passive"))
      (node (ref "TP5") (pin "TP") (pinfunction "TP_TP") (pintype "input"))
    )
    (net (code "23") (name "Net-(IC1A-S0)") (class "Default")
      (node (ref "IC1") (pin "4") (pinfunction "S0_4") (pintype "input"))
      (node (ref "LED6") (pin "C") (pinfunction "C_C") (pintype "passive"))
      (node (ref "OK2") (pin "6") (pinfunction "VO_6") (pintype "passive"))
      (node (ref "TP1") (pin "TP") (pinfunction "TP_TP") (pintype "input"))
    )
    (net (code "24") (name "Net-(IC1A-S1)") (class "Default")
      (node (ref "C9") (pin "1") (pinfunction "1_1") (pintype "passive"))
      (node (ref "IC1") (pin "6") (pinfunction "S1_6") (pintype "input"))
      (node (ref "R2") (pin "2") (pinfunction "2_2") (pintype "passive"))
      (node (ref "TP12") (pin "TP") (pinfunction "TP_TP") (pintype "input"))
    )
    (net (code "25") (name "Net-(IC2-CV)") (class "Default")
      (node (ref "C6") (pin "1") (pinfunction "1_1") (pintype "passive"))
      (node (ref "IC2") (pin "5") (pinfunction "CV_5") (pintype "input"))
    )
    (net (code "26") (name "Net-(IC2-DIS)") (class "Default")
      (node (ref "C7") (pin "1") (pinfunction "1_1") (pintype "passive"))
      (node (ref "IC2") (pin "6") (pinfunction "THR_6") (pintype "input"))
      (node (ref "IC2") (pin "7") (pinfunction "DIS_7") (pintype "input"))
      (node (ref "R5") (pin "1") (pinfunction "1_1") (pintype "passive"))
    )
    (net (code "27") (name "Net-(IC2-TR)") (class "Default")
      (node (ref "C8") (pin "1") (pinfunction "1_1") (pintype "passive"))
      (node (ref "IC2") (pin "2") (pinfunction "TR_2") (pintype "input"))
      (node (ref "R10") (pin "1") (pinfunction "1_1") (pintype "passive"))
      (node (ref "R11") (pin "2") (pinfunction "2_2") (pintype "passive"))
    )
    (net (code "28") (name "Net-(IC9A-O)") (class "Default")
      (node (ref "IC9") (pin "3") (pinfunction "O_3") (pintype "output"))
      (node (ref "Q2") (pin "1") (pinfunction "G_1") (pintype "passive"))
      (node (ref "R24") (pin "2") (pinfunction "2_2") (pintype "passive"))
      (node (ref "TP17") (pin "TP") (pinfunction "TP_TP") (pintype "input"))
    )
    (net (code "29") (name "Net-(IC9B-O)") (class "Default")
      (node (ref "IC9") (pin "4") (pinfunction "O_4") (pintype "output"))
      (node (ref "Q4") (pin "1") (pinfunction "G_1") (pintype "passive"))
      (node (ref "R19") (pin "2") (pinfunction "2_2") (pintype "passive"))
      (node (ref "TP2") (pin "TP") (pinfunction "TP_TP") (pintype "input"))
    )
    (net (code "30") (name "Net-(IC9C-I0)") (class "Default")
      (node (ref "IC9") (pin "11") (pinfunction "O_11") (pintype "output"))
      (node (ref "IC9") (pin "8") (pinfunction "I0_8") (pintype "input"))
      (node (ref "IC9") (pin "9") (pinfunction "I1_9") (pintype "input"))
      (node (ref "TP11") (pin "TP") (pinfunction "TP_TP") (pintype "input"))
    )
    (net (code "31") (name "Net-(IC9C-O)") (class "Default")
      (node (ref "IC9") (pin "10") (pinfunction "O_10") (pintype "output"))
      (node (ref "R2") (pin "1") (pinfunction "1_1") (pintype "passive"))
      (node (ref "TP16") (pin "TP") (pinfunction "TP_TP") (pintype "input"))
    )
    (net (code "32") (name "Net-(K6-COIL_2)") (class "Default")
      (node (ref "D7") (pin "A") (pinfunction "A_A") (pintype "passive"))
      (node (ref "K6") (pin "2") (pinfunction "COIL_2_2") (pintype "bidirectional"))
      (node (ref "LED7") (pin "C") (pinfunction "C_C") (pintype "passive"))
      (node (ref "Q4") (pin "3") (pinfunction "D_3") (pintype "passive"))
      (node (ref "TP21") (pin "TP") (pinfunction "TP_TP") (pintype "input"))
    )
    (net (code "33") (name "Net-(K6-NO)") (class "Default")
      (node (ref "K6") (pin "4") (pinfunction "NO_4") (pintype "bidirectional"))
      (node (ref "K7") (pin "3") (pinfunction "COM_3") (pintype "bidirectional"))
    )
    (net (code "34") (name "Net-(K7-COIL_2)") (class "Default")
      (node (ref "D8") (pin "A") (pinfunction "A_A") (pintype "passive"))
      (node (ref "K7") (pin "2") (pinfunction "COIL_2_2") (pintype "bidirectional"))
      (node (ref "LED8") (pin "C") (pinfunction "C_C") (pintype "passive"))
      (node (ref "Q2") (pin "3") (pinfunction "D_3") (pintype "passive"))
      (node (ref "TP14") (pin "TP") (pinfunction "TP_TP") (pintype "input"))
    )
    (net (code "35") (name "Net-(LED1-PadA)") (class "Default")
      (node (ref "LED1") (pin "A") (pinfunction "A_A") (pintype "passive"))
      (node (ref "R20") (pin "2") (pinfunction "2_2") (pintype "passive"))
    )
    (net (code "36") (name "Net-(LED2-PadA)") (class "Default")
      (node (ref "LED2") (pin "A") (pinfunction "A_A") (pintype "passive"))
      (node (ref "R21") (pin "2") (pinfunction "2_2") (pintype "passive"))
    )
    (net (code "37") (name "Net-(LED3-PadA)") (class "Default")
      (node (ref "LED3") (pin "A") (pinfunction "A_A") (pintype "passive"))
      (node (ref "R22") (pin "2") (pinfunction "2_2") (pintype "passive"))
    )
    (net (code "38") (name "Net-(LED4-PadA)") (class "Default")
      (node (ref "LED4") (pin "A") (pinfunction "A_A") (pintype "passive"))
      (node (ref "R7") (pin "2") (pinfunction "2_2") (pintype "passive"))
    )
    (net (code "39") (name "Net-(LED5-PadA)") (class "Default")
      (node (ref "LED5") (pin "A") (pinfunction "A_A") (pintype "passive"))
      (node (ref "R6") (pin "2") (pinfunction "2_2") (pintype "passive"))
    )
    (net (code "40") (name "Net-(LED6-PadA)") (class "Default")
      (node (ref "LED6") (pin "A") (pinfunction "A_A") (pintype "passive"))
      (node (ref "R8") (pin "2") (pinfunction "2_2") (pintype "passive"))
    )
    (net (code "41") (name "Net-(LED7-PadA)") (class "Default")
      (node (ref "LED7") (pin "A") (pinfunction "A_A") (pintype "passive"))
      (node (ref "R14") (pin "1") (pinfunction "1_1") (pintype "passive"))
    )
    (net (code "42") (name "Net-(LED8-PadA)") (class "Default")
      (node (ref "LED8") (pin "A") (pinfunction "A_A") (pintype "passive"))
      (node (ref "R15") (pin "1") (pinfunction "1_1") (pintype "passive"))
    )
    (net (code "43") (name "Net-(OK2-C)") (class "Default")
      (node (ref "OK2") (pin "3") (pinfunction "C_3") (pintype "passive"))
      (node (ref "R3") (pin "1") (pinfunction "1_1") (pintype "passive"))
    )
    (net (code "44") (name "Net-(POWER/GNDA-S)") (class "Default")
      (node (ref "F1") (pin "2") (pinfunction "2_2") (pintype "bidirectional"))
      (node (ref "POWER/GND") (pin "1") (pinfunction "S_1") (pintype "passive"))
    )
    (net (code "45") (name "Net-(POWER/GNDB-S)") (class "Default")
      (node (ref "F2") (pin "2") (pinfunction "2_2") (pintype "bidirectional"))
      (node (ref "POWER/GND") (pin "2") (pinfunction "S_2") (pintype "passive"))
    )
    (net (code "46") (name "Net-(PRECHARGE/AIRSA-S)") (class "Default")
      (node (ref "K2") (pin "2") (pinfunction "2_2") (pintype "bidirectional"))
      (node (ref "PRECHARGE/AIRS") (pin "1") (pinfunction "S_1") (pintype "passive"))
    )
    (net (code "47") (name "Net-(PRECHARGE/AIRSB-S)") (class "Default")
      (node (ref "K2") (pin "3") (pinfunction "3_3") (pintype "bidirectional"))
      (node (ref "PRECHARGE/AIRS") (pin "2") (pinfunction "S_2") (pintype "passive"))
    )
    (net (code "48") (name "OK_HS") (class "Default")
      (node (ref "ISOMETER_I/O") (pin "8") (pinfunction "8_8") (pintype "passive"))
      (node (ref "OK2") (pin "2") (pinfunction "A_2") (pintype "passive"))
      (node (ref "TP10") (pin "TP") (pinfunction "TP_TP") (pintype "input"))
    )
    (net (code "49") (name "PRECHARGE_EMSDC1") (class "Default")
      (node (ref "K6") (pin "3") (pinfunction "COM_3") (pintype "bidirectional"))
      (node (ref "PRECHARGE") (pin "1") (pinfunction "1_1") (pintype "passive"))
    )
    (net (code "50") (name "PRECHARGE_EMSDC2") (class "Default")
      (node (ref "EMSDC") (pin "1") (pinfunction "S_1") (pintype "passive"))
      (node (ref "PRECHARGE") (pin "2") (pinfunction "2_2") (pintype "passive"))
    )
    (net (code "51") (name "PRECHARGE_SELECT") (class "Default")
      (node (ref "BMS_I/O") (pin "7") (pinfunction "7_7") (pintype "passive"))
      (node (ref "D1") (pin "A") (pinfunction "A_A") (pintype "passive"))
      (node (ref "K2") (pin "5") (pinfunction "5_5") (pintype "bidirectional"))
      (node (ref "LED1") (pin "C") (pinfunction "C_C") (pintype "passive"))
      (node (ref "PRECHARGE") (pin "3") (pinfunction "3_3") (pintype "passive"))
      (node (ref "TP23") (pin "TP") (pinfunction "TP_TP") (pintype "input"))
    )
    (net (code "52") (name "READY_POWER") (class "Default")
      (node (ref "BMS_POWER/GND") (pin "1") (pinfunction "S_1") (pintype "passive"))
      (node (ref "D2") (pin "2") (pinfunction "A_2") (pintype "bidirectional"))
      (node (ref "F2") (pin "1") (pinfunction "1_1") (pintype "bidirectional"))
      (node (ref "PRECHARGE") (pin "8") (pinfunction "8_8") (pintype "passive"))
      (node (ref "THERMAL_EX_I/0") (pin "1") (pinfunction "1_1") (pintype "passive"))
      (node (ref "WIFI_MODULE") (pin "1") (pinfunction "1_1") (pintype "passive"))
    )
    (net (code "53") (name "STARTUP_RESET") (class "Default")
      (node (ref "IC1") (pin "3") (pinfunction "R0_3") (pintype "input"))
      (node (ref "IC1") (pin "7") (pinfunction "R1_7") (pintype "input"))
      (node (ref "IC2") (pin "3") (pinfunction "Q_3") (pintype "output"))
      (node (ref "R9") (pin "2") (pinfunction "2_2") (pintype "passive"))
      (node (ref "TP4") (pin "TP") (pinfunction "TP_TP") (pintype "input"))
    )
    (net (code "54") (name "unconnected-(CAN1-Pad1)") (class "Default")
      (node (ref "CAN1") (pin "1") (pinfunction "1_1") (pintype "bidirectional"))
    )
    (net (code "55") (name "unconnected-(CAN1-Pad2)") (class "Default")
      (node (ref "CAN1") (pin "2") (pinfunction "2_2") (pintype "bidirectional"))
    )
    (net (code "56") (name "unconnected-(CAN1-Pad4)") (class "Default")
      (node (ref "CAN1") (pin "4") (pinfunction "4_4") (pintype "bidirectional"))
    )
    (net (code "57") (name "unconnected-(CAN1-Pad6)") (class "Default")
      (node (ref "CAN1") (pin "6") (pinfunction "6_6") (pintype "bidirectional"))
    )
    (net (code "58") (name "unconnected-(CAN1-Pad7)") (class "Default")
      (node (ref "CAN1") (pin "7") (pinfunction "7_7") (pintype "bidirectional"))
    )
    (net (code "59") (name "unconnected-(CAN1-Pad8)") (class "Default")
      (node (ref "CAN1") (pin "8") (pinfunction "8_8") (pintype "bidirectional"))
    )
    (net (code "60") (name "unconnected-(CAN1-Pad9)") (class "Default")
      (node (ref "CAN1") (pin "9") (pinfunction "9_9") (pintype "bidirectional"))
    )
    (net (code "61") (name "unconnected-(CAN1-PadMH1)") (class "Default")
      (node (ref "CAN1") (pin "MH1") (pinfunction "MH1_MH1") (pintype "bidirectional"))
    )
    (net (code "62") (name "unconnected-(CAN1-PadMH2)") (class "Default")
      (node (ref "CAN1") (pin "MH2") (pinfunction "MH2_MH2") (pintype "bidirectional"))
    )
    (net (code "63") (name "unconnected-(CAN2-Pad1)") (class "Default")
      (node (ref "CAN2") (pin "1") (pinfunction "1_1") (pintype "bidirectional"))
    )
    (net (code "64") (name "unconnected-(CAN2-Pad2)") (class "Default")
      (node (ref "CAN2") (pin "2") (pinfunction "2_2") (pintype "bidirectional"))
    )
    (net (code "65") (name "unconnected-(CAN2-Pad4)") (class "Default")
      (node (ref "CAN2") (pin "4") (pinfunction "4_4") (pintype "bidirectional"))
    )
    (net (code "66") (name "unconnected-(CAN2-Pad6)") (class "Default")
      (node (ref "CAN2") (pin "6") (pinfunction "6_6") (pintype "bidirectional"))
    )
    (net (code "67") (name "unconnected-(CAN2-Pad7)") (class "Default")
      (node (ref "CAN2") (pin "7") (pinfunction "7_7") (pintype "bidirectional"))
    )
    (net (code "68") (name "unconnected-(CAN2-Pad8)") (class "Default")
      (node (ref "CAN2") (pin "8") (pinfunction "8_8") (pintype "bidirectional"))
    )
    (net (code "69") (name "unconnected-(CAN2-Pad9)") (class "Default")
      (node (ref "CAN2") (pin "9") (pinfunction "9_9") (pintype "bidirectional"))
    )
    (net (code "70") (name "unconnected-(CAN2-PadMH1)") (class "Default")
      (node (ref "CAN2") (pin "MH1") (pinfunction "MH1_MH1") (pintype "bidirectional"))
    )
    (net (code "71") (name "unconnected-(CAN2-PadMH2)") (class "Default")
      (node (ref "CAN2") (pin "MH2") (pinfunction "MH2_MH2") (pintype "bidirectional"))
    )
    (net (code "72") (name "unconnected-(EMSDC1A-S-Pad1)") (class "Default")
      (node (ref "EMSDC1") (pin "1") (pinfunction "S_1") (pintype "passive"))
    )
    (net (code "73") (name "unconnected-(EMSDC1B-S-Pad2)") (class "Default")
      (node (ref "EMSDC1") (pin "2") (pinfunction "S_2") (pintype "passive"))
    )
    (net (code "74") (name "unconnected-(EMSDC1C-S-Pad3)") (class "Default")
      (node (ref "EMSDC1") (pin "3") (pinfunction "S_3") (pintype "passive"))
    )
    (net (code "75") (name "unconnected-(EMSDC1D-S-Pad4)") (class "Default")
      (node (ref "EMSDC1") (pin "4") (pinfunction "S_4") (pintype "passive"))
    )
    (net (code "76") (name "unconnected-(EMSDC1E-S-Pad5)") (class "Default")
      (node (ref "EMSDC1") (pin "5") (pinfunction "S_5") (pintype "passive"))
    )
    (net (code "77") (name "unconnected-(EMSDC1F-S-Pad6)") (class "Default")
      (node (ref "EMSDC1") (pin "6") (pinfunction "S_6") (pintype "passive"))
    )
    (net (code "78") (name "unconnected-(IC1A-Q2-Pad10)") (class "Default")
      (node (ref "IC1") (pin "10") (pinfunction "Q2_10") (pintype "output"))
    )
    (net (code "79") (name "unconnected-(IC1A-Q3-Pad1)") (class "Default")
      (node (ref "IC1") (pin "1") (pinfunction "Q3_1") (pintype "output"))
    )
    (net (code "80") (name "unconnected-(IC4A-~{SHDN}-Pad5)") (class "Default")
      (node (ref "IC4") (pin "5") (pinfunction "~{SHDN}_5") (pintype "input"))
    )
    (net (code "81") (name "unconnected-(ISOMETER_I/O-Pad4)") (class "Default")
      (node (ref "ISOMETER_I/O") (pin "4") (pinfunction "4_4") (pintype "passive"))
    )
    (net (code "82") (name "unconnected-(ISOMETER_I/O-Pad6)") (class "Default")
      (node (ref "ISOMETER_I/O") (pin "6") (pinfunction "6_6") (pintype "passive"))
    )
    (net (code "83") (name "unconnected-(ISOMETER_I/O-Pad7)") (class "Default")
      (node (ref "ISOMETER_I/O") (pin "7") (pinfunction "7_7") (pintype "passive"))
    )
    (net (code "84") (name "unconnected-(THERMAL_EX_I/0-Pad7)") (class "Default")
      (node (ref "THERMAL_EX_I/0") (pin "7") (pinfunction "7_7") (pintype "passive"))
    )
    (net (code "85") (name "unconnected-(WIFI_MODULE-Pad4)") (class "Default")
      (node (ref "WIFI_MODULE") (pin "4") (pinfunction "4_4") (pintype "passive"))
    )
    (net (code "86") (name "unconnected-(WIFI_MODULE-Pad6)") (class "Default")
      (node (ref "WIFI_MODULE") (pin "6") (pinfunction "6_6") (pintype "passive"))
    )
    (net (code "87") (name "unconnected-(WIFI_MODULE-Pad7)") (class "Default")
      (node (ref "WIFI_MODULE") (pin "7") (pinfunction "7_7") (pintype "passive"))
    )
  )
)
